# sawbench_digital_reva.net
KiCad netlist of a schematic drawn in EAGLE
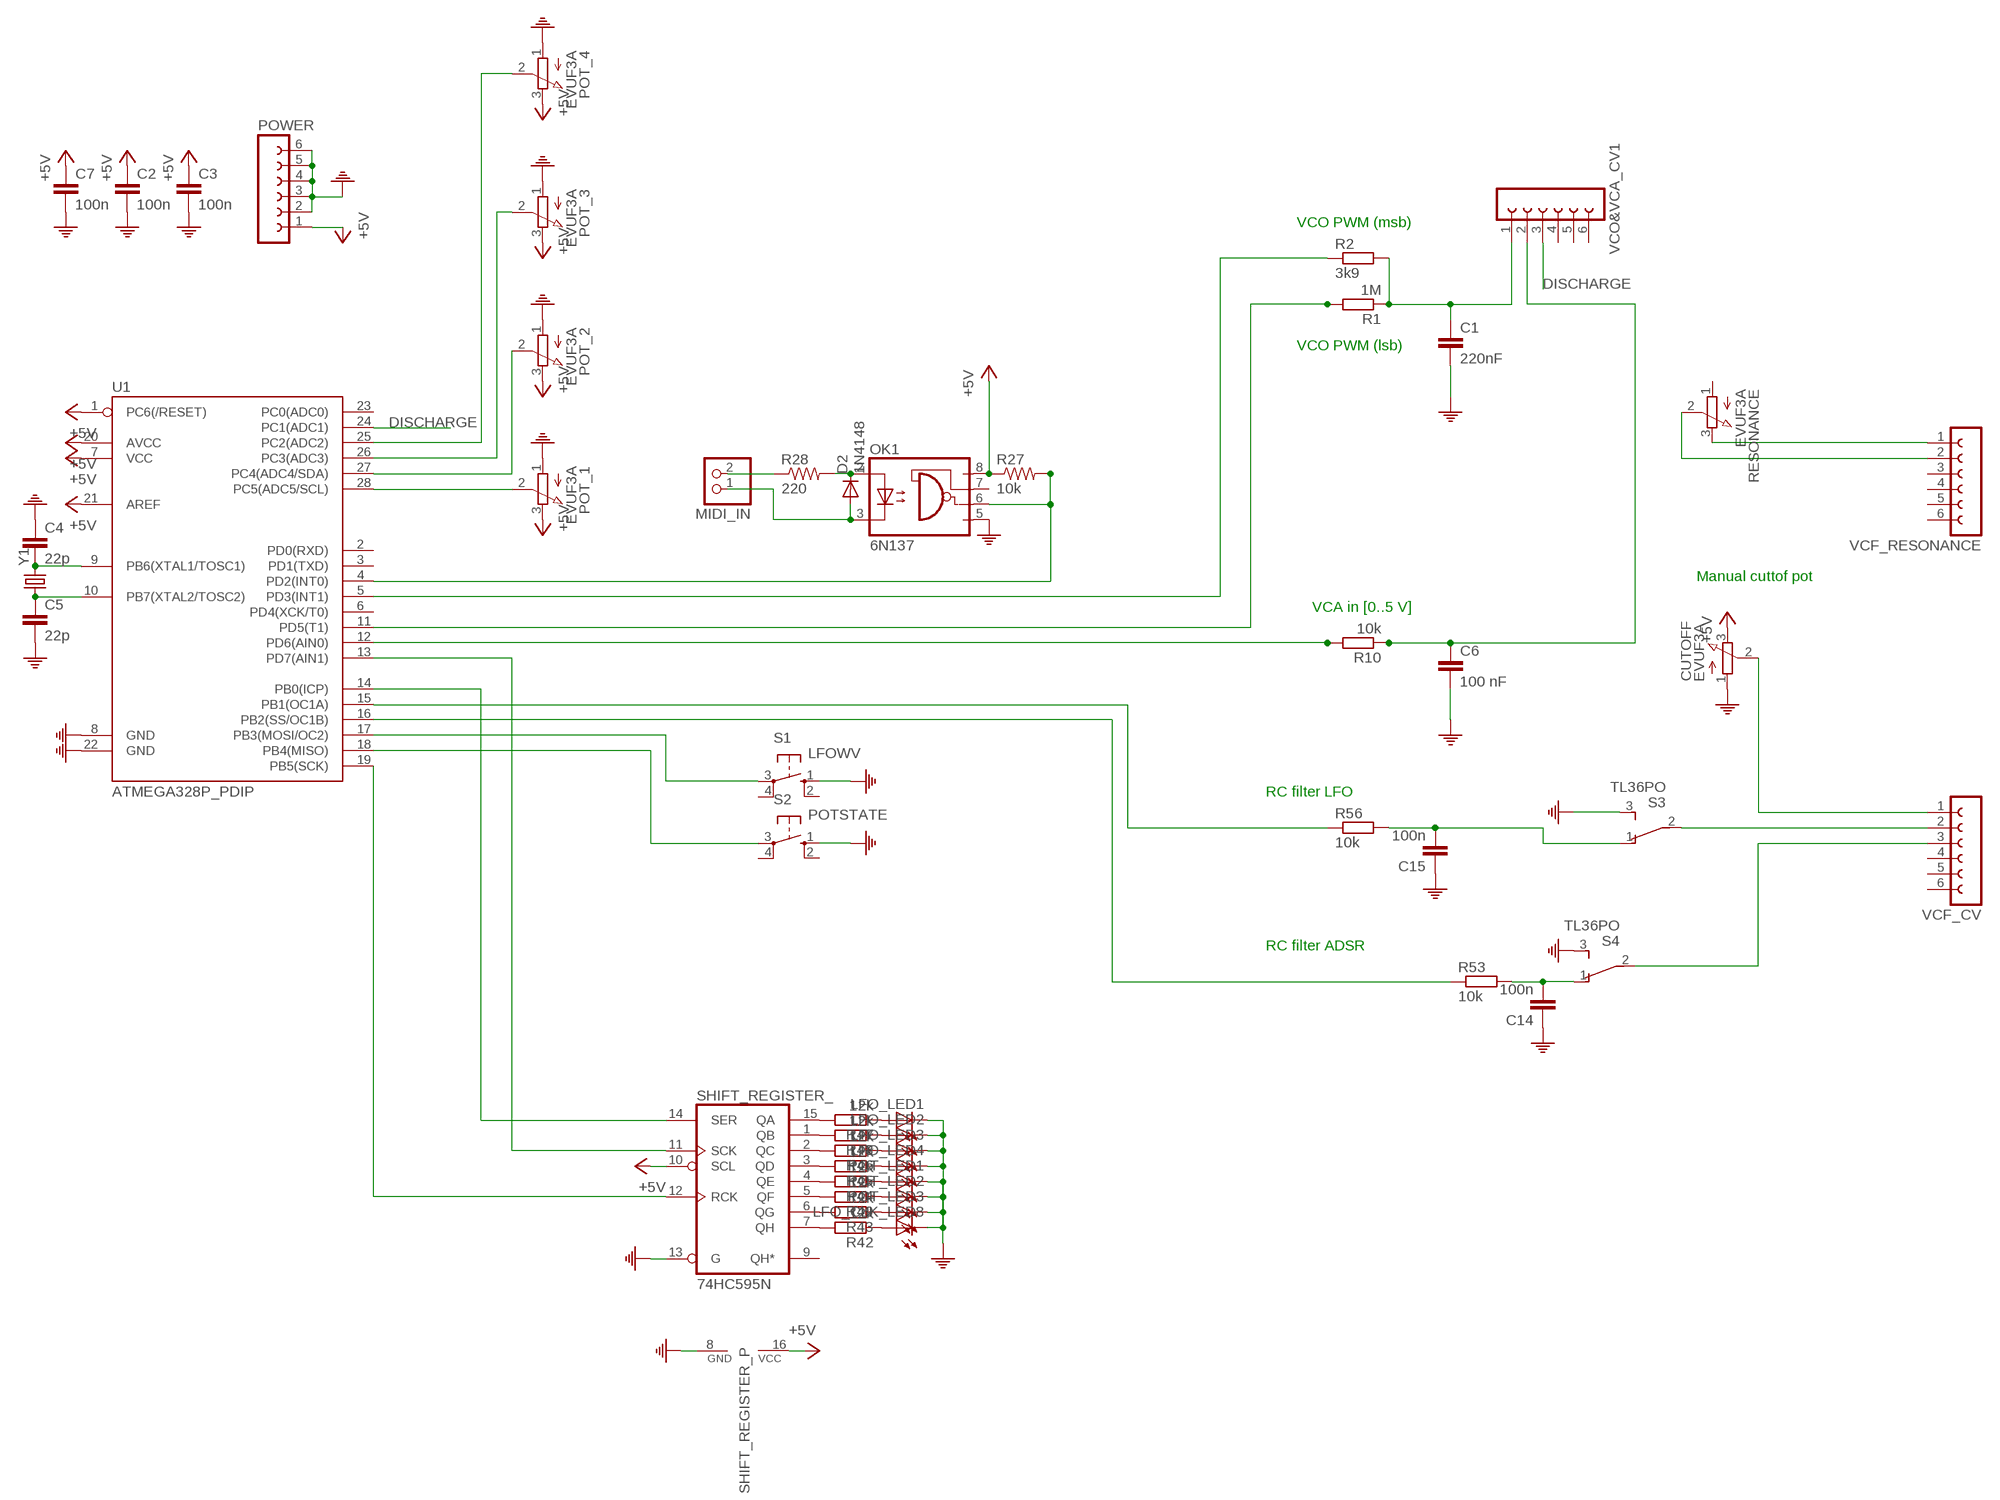
[diagram p0: schematic, sheet 1]

(export (version "E")
  (design (tool "Eeschema 10.0.6"))
  (components
    (comp (ref "C1")
      (value "220nF")
      (footprint "eagle-import:C050-024X044")
      (libsource (lib "eagle-import") (part "resistor_C-EU050-024X044"))
    )
    (comp (ref "C2")
      (value "100n")
      (footprint "eagle-import:C025-024X044")
      (libsource (lib "eagle-import") (part "C-EU025-024X044"))
    )
    (comp (ref "C3")
      (value "100n")
      (footprint "eagle-import:C025-024X044")
      (libsource (lib "eagle-import") (part "C-EU025-024X044"))
    )
    (comp (ref "C4")
      (value "22p")
      (footprint "eagle-import:C025-024X044")
      (libsource (lib "eagle-import") (part "C-EU025-024X044"))
    )
    (comp (ref "C5")
      (value "22p")
      (footprint "eagle-import:C025-024X044")
      (libsource (lib "eagle-import") (part "C-EU025-024X044"))
    )
    (comp (ref "C6")
      (value "100 nF")
      (footprint "eagle-import:C025-025X050")
      (libsource (lib "eagle-import") (part "C-EU025-025X050"))
    )
    (comp (ref "C7")
      (value "100n")
      (footprint "eagle-import:C025-024X044")
      (libsource (lib "eagle-import") (part "C-EU025-024X044"))
    )
    (comp (ref "C14")
      (value "100n")
      (footprint "eagle-import:C025-024X044")
      (libsource (lib "eagle-import") (part "resistor_C-EU025-024X044"))
    )
    (comp (ref "C15")
      (value "100n")
      (footprint "eagle-import:C025-024X044")
      (libsource (lib "eagle-import") (part "resistor_C-EU025-024X044"))
    )
    (comp (ref "CUTOFF")
      (value "EVUF3A")
      (footprint "eagle-import:EVUF")
      (libsource (lib "eagle-import") (part "EVUAF3"))
    )
    (comp (ref "D2")
      (value "1N4148")
      (footprint "eagle-import:D-5")
      (libsource (lib "eagle-import") (part "DIODE-D-5"))
    )
    (comp (ref "LFO_CLK_LED8")
      (value "LED3MM")
      (footprint "eagle-import:LED3MM")
      (libsource (lib "eagle-import") (part "LED3MM"))
    )
    (comp (ref "LFO_LED1")
      (value "LED3MM")
      (footprint "eagle-import:LED3MM")
      (libsource (lib "eagle-import") (part "LED3MM"))
    )
    (comp (ref "LFO_LED2")
      (value "LED3MM")
      (footprint "eagle-import:LED3MM")
      (libsource (lib "eagle-import") (part "LED3MM"))
    )
    (comp (ref "LFO_LED3")
      (value "LED3MM")
      (footprint "eagle-import:LED3MM")
      (libsource (lib "eagle-import") (part "LED3MM"))
    )
    (comp (ref "LFO_LED4")
      (value "LED3MM")
      (footprint "eagle-import:LED3MM")
      (libsource (lib "eagle-import") (part "LED3MM"))
    )
    (comp (ref "MIDI_IN")
      (value "PINHD-1X2")
      (footprint "eagle-import:1X02")
      (libsource (lib "eagle-import") (part "PINHD-1X2"))
    )
    (comp (ref "OK1")
      (value "6N137")
      (footprint "eagle-import:DIL08")
      (libsource (lib "eagle-import") (part "6N137"))
    )
    (comp (ref "POT_1")
      (value "EVUF3A")
      (footprint "eagle-import:EVUF")
      (libsource (lib "eagle-import") (part "EVUAF3"))
    )
    (comp (ref "POT_2")
      (value "EVUF3A")
      (footprint "eagle-import:EVUF")
      (libsource (lib "eagle-import") (part "EVUAF3"))
    )
    (comp (ref "POT_3")
      (value "EVUF3A")
      (footprint "eagle-import:EVUF")
      (libsource (lib "eagle-import") (part "EVUAF3"))
    )
    (comp (ref "POT_4")
      (value "EVUF3A")
      (footprint "eagle-import:EVUF")
      (libsource (lib "eagle-import") (part "EVUAF3"))
    )
    (comp (ref "POT_LED1")
      (value "LED3MM")
      (footprint "eagle-import:LED3MM")
      (libsource (lib "eagle-import") (part "LED3MM"))
    )
    (comp (ref "POT_LED2")
      (value "LED3MM")
      (footprint "eagle-import:LED3MM")
      (libsource (lib "eagle-import") (part "LED3MM"))
    )
    (comp (ref "POT_LED3")
      (value "LED3MM")
      (footprint "eagle-import:LED3MM")
      (libsource (lib "eagle-import") (part "LED3MM"))
    )
    (comp (ref "POWER")
      (value "FE06-1")
      (footprint "eagle-import:FE06")
      (libsource (lib "eagle-import") (part "FE06-1"))
    )
    (comp (ref "R1")
      (value "1M")
      (footprint "eagle-import:0204_7")
      (libsource (lib "eagle-import") (part "R-EU_0204/7"))
    )
    (comp (ref "R2")
      (value "3k9")
      (footprint "eagle-import:0204_7")
      (libsource (lib "eagle-import") (part "R-EU_0204/7"))
    )
    (comp (ref "R10")
      (value "10k")
      (footprint "eagle-import:0204_7")
      (libsource (lib "eagle-import") (part "R-EU_0204/7"))
    )
    (comp (ref "R27")
      (value "10k")
      (footprint "eagle-import:0204_7")
      (libsource (lib "eagle-import") (part "R-US_0204/7"))
    )
    (comp (ref "R28")
      (value "220")
      (footprint "eagle-import:0204_7")
      (libsource (lib "eagle-import") (part "R-US_0204/7"))
    )
    (comp (ref "R42")
      (value "12k")
      (footprint "eagle-import:0204_7")
      (libsource (lib "eagle-import") (part "R-EU_0204/7"))
    )
    (comp (ref "R43")
      (value "12k")
      (footprint "eagle-import:0204_7")
      (libsource (lib "eagle-import") (part "R-EU_0204/7"))
    )
    (comp (ref "R44")
      (value "12k")
      (footprint "eagle-import:0204_7")
      (libsource (lib "eagle-import") (part "R-EU_0204/7"))
    )
    (comp (ref "R45")
      (value "12k")
      (footprint "eagle-import:0204_7")
      (libsource (lib "eagle-import") (part "R-EU_0204/7"))
    )
    (comp (ref "R46")
      (value "12k")
      (footprint "eagle-import:0204_7")
      (libsource (lib "eagle-import") (part "R-EU_0204/7"))
    )
    (comp (ref "R47")
      (value "12k")
      (footprint "eagle-import:0204_7")
      (libsource (lib "eagle-import") (part "R-EU_0204/7"))
    )
    (comp (ref "R48")
      (value "12k")
      (footprint "eagle-import:0204_7")
      (libsource (lib "eagle-import") (part "R-EU_0204/7"))
    )
    (comp (ref "R49")
      (value "12k")
      (footprint "eagle-import:0204_7")
      (libsource (lib "eagle-import") (part "R-EU_0204/7"))
    )
    (comp (ref "R53")
      (value "10k")
      (footprint "eagle-import:0204_7")
      (libsource (lib "eagle-import") (part "R-EU_0204/7"))
    )
    (comp (ref "R56")
      (value "10k")
      (footprint "eagle-import:0204_7")
      (libsource (lib "eagle-import") (part "R-EU_0204/7"))
    )
    (comp (ref "RESONANCE")
      (value "EVUF3A")
      (footprint "eagle-import:EVUF")
      (libsource (lib "eagle-import") (part "EVUAF3"))
    )
    (comp (ref "S1")
      (value "LFOWV")
      (footprint "eagle-import:B3F-10XX(TASTYSWITCH)")
      (fields (field (name "MPN") "B3F-1000"))
      (libsource (lib "eagle-import") (part "10-XX"))
    )
    (comp (ref "S2")
      (value "POTSTATE")
      (footprint "eagle-import:B3F-10XX(TASTYSWITCH)")
      (fields (field (name "MPN") "B3F-1000"))
      (libsource (lib "eagle-import") (part "10-XX"))
    )
    (comp (ref "S3")
      (value "TL36PO")
      (footprint "eagle-import:TL3XPO(TASTY_CHIPS_UPDATE)")
      (libsource (lib "eagle-import") (part "TL36PO"))
    )
    (comp (ref "S4")
      (value "TL36PO")
      (footprint "eagle-import:TL3XPO(TASTY_CHIPS_UPDATE)")
      (libsource (lib "eagle-import") (part "TL36PO"))
    )
    (comp (ref "SHIFT_REGISTER_")
      (value "74HC595N")
      (footprint "eagle-import:DIL16")
      (libsource (lib "eagle-import") (part "74595NHC"))
    )
    (comp (ref "U1")
      (value "ATMEGA328P_PDIP")
      (footprint "eagle-import:DIL28-3")
      (libsource (lib "eagle-import") (part "ATMEGA328P_PDIP"))
    )
    (comp (ref "VCF_CV")
      (value "FE06-1")
      (footprint "eagle-import:FE06")
      (libsource (lib "eagle-import") (part "FE06-1"))
    )
    (comp (ref "VCF_RESONANCE")
      (value "FE06-1")
      (footprint "eagle-import:FE06")
      (libsource (lib "eagle-import") (part "FE06-1"))
    )
    (comp (ref "VCO&VCA_CV1")
      (value "FE06-1")
      (footprint "eagle-import:FE06")
      (libsource (lib "eagle-import") (part "FE06-1"))
    )
    (comp (ref "Y1")
      (value "CRYSTALHC49S")
      (footprint "eagle-import:HC49_S")
      (libsource (lib "eagle-import") (part "CRYSTALHC49S"))
    )
  )
  (nets
    (net (code "1") (name "+5V") (class "Default")
      (node (ref "C2") (pin "1") (pinfunction "1_1") (pintype "passive"))
      (node (ref "C3") (pin "1") (pinfunction "1_1") (pintype "passive"))
      (node (ref "C7") (pin "1") (pinfunction "1_1") (pintype "passive"))
      (node (ref "CUTOFF") (pin "3") (pinfunction "E_3") (pintype "passive"))
      (node (ref "OK1") (pin "8") (pinfunction "VCC_8") (pintype "passive"))
      (node (ref "POT_1") (pin "3") (pinfunction "E_3") (pintype "passive"))
      (node (ref "POT_2") (pin "3") (pinfunction "E_3") (pintype "passive"))
      (node (ref "POT_3") (pin "3") (pinfunction "E_3") (pintype "passive"))
      (node (ref "POT_4") (pin "3") (pinfunction "E_3") (pintype "passive"))
      (node (ref "POWER") (pin "1") (pinfunction "1_1") (pintype "passive"))
      (node (ref "R27") (pin "1") (pinfunction "1_1") (pintype "passive"))
      (node (ref "SHIFT_REGISTER_") (pin "10") (pinfunction "SCL_10") (pintype "input"))
      (node (ref "SHIFT_REGISTER_") (pin "16") (pinfunction "VCC_16") (pintype "power_in"))
      (node (ref "U1") (pin "1") (pinfunction "PC6(/RESET)_1") (pintype "bidirectional"))
      (node (ref "U1") (pin "20") (pinfunction "AVCC_20") (pintype "bidirectional"))
      (node (ref "U1") (pin "21") (pinfunction "AREF_21") (pintype "bidirectional"))
      (node (ref "U1") (pin "7") (pinfunction "VCC_7") (pintype "bidirectional"))
    )
    (net (code "2") (name "/DISCHARGE") (class "Default")
      (node (ref "U1") (pin "24") (pinfunction "PC1(ADC1)_24") (pintype "bidirectional"))
      (node (ref "VCO&VCA_CV1") (pin "3") (pinfunction "3_3") (pintype "passive"))
    )
    (net (code "3") (name "Net-(C1-Pad1)") (class "Default")
      (node (ref "C1") (pin "1") (pinfunction "1_1") (pintype "passive"))
      (node (ref "R1") (pin "1") (pinfunction "1_1") (pintype "passive"))
      (node (ref "R2") (pin "2") (pinfunction "2_2") (pintype "passive"))
      (node (ref "VCO&VCA_CV1") (pin "1") (pinfunction "1_1") (pintype "passive"))
    )
    (net (code "4") (name "Net-(C6-Pad1)") (class "Default")
      (node (ref "C6") (pin "1") (pinfunction "1_1") (pintype "passive"))
      (node (ref "R10") (pin "1") (pinfunction "1_1") (pintype "passive"))
      (node (ref "VCO&VCA_CV1") (pin "2") (pinfunction "2_2") (pintype "passive"))
    )
    (net (code "5") (name "Net-(CUTOFF-S)") (class "Default")
      (node (ref "CUTOFF") (pin "2") (pinfunction "S_2") (pintype "passive"))
      (node (ref "VCF_CV") (pin "1") (pinfunction "1_1") (pintype "passive"))
    )
    (net (code "6") (name "Net-(LFO_CLK_LED8-PadA)") (class "Default")
      (node (ref "LFO_CLK_LED8") (pin "A") (pinfunction "A_A") (pintype "passive"))
      (node (ref "R42") (pin "1") (pinfunction "1_1") (pintype "passive"))
    )
    (net (code "7") (name "Net-(LFO_LED1-PadA)") (class "Default")
      (node (ref "LFO_LED1") (pin "A") (pinfunction "A_A") (pintype "passive"))
      (node (ref "R47") (pin "1") (pinfunction "1_1") (pintype "passive"))
    )
    (net (code "8") (name "Net-(LFO_LED2-PadA)") (class "Default")
      (node (ref "LFO_LED2") (pin "A") (pinfunction "A_A") (pintype "passive"))
      (node (ref "R48") (pin "1") (pinfunction "1_1") (pintype "passive"))
    )
    (net (code "9") (name "Net-(LFO_LED3-PadA)") (class "Default")
      (node (ref "LFO_LED3") (pin "A") (pinfunction "A_A") (pintype "passive"))
      (node (ref "R46") (pin "1") (pinfunction "1_1") (pintype "passive"))
    )
    (net (code "10") (name "Net-(LFO_LED4-PadA)") (class "Default")
      (node (ref "LFO_LED4") (pin "A") (pinfunction "A_A") (pintype "passive"))
      (node (ref "R45") (pin "1") (pinfunction "1_1") (pintype "passive"))
    )
    (net (code "11") (name "Net-(MIDI_IN-Pad2)") (class "Default")
      (node (ref "MIDI_IN") (pin "2") (pinfunction "2_2") (pintype "passive"))
      (node (ref "R28") (pin "1") (pinfunction "1_1") (pintype "passive"))
    )
    (net (code "12") (name "Net-(OK1-A)") (class "Default")
      (node (ref "D2") (pin "C") (pinfunction "C_C") (pintype "passive"))
      (node (ref "OK1") (pin "2") (pinfunction "A_2") (pintype "passive"))
      (node (ref "R28") (pin "2") (pinfunction "2_2") (pintype "passive"))
    )
    (net (code "13") (name "Net-(OK1-C)") (class "Default")
      (node (ref "D2") (pin "A") (pinfunction "A_A") (pintype "passive"))
      (node (ref "MIDI_IN") (pin "1") (pinfunction "1_1") (pintype "passive"))
      (node (ref "OK1") (pin "3") (pinfunction "C_3") (pintype "passive"))
    )
    (net (code "14") (name "Net-(OK1-VO)") (class "Default")
      (node (ref "OK1") (pin "6") (pinfunction "VO_6") (pintype "passive"))
      (node (ref "R27") (pin "2") (pinfunction "2_2") (pintype "passive"))
      (node (ref "U1") (pin "4") (pinfunction "PD2(INT0)_4") (pintype "bidirectional"))
    )
    (net (code "15") (name "Net-(POT_1-S)") (class "Default")
      (node (ref "POT_1") (pin "2") (pinfunction "S_2") (pintype "passive"))
      (node (ref "U1") (pin "28") (pinfunction "PC5(ADC5/SCL)_28") (pintype "bidirectional"))
    )
    (net (code "16") (name "Net-(POT_2-S)") (class "Default")
      (node (ref "POT_2") (pin "2") (pinfunction "S_2") (pintype "passive"))
      (node (ref "U1") (pin "27") (pinfunction "PC4(ADC4/SDA)_27") (pintype "bidirectional"))
    )
    (net (code "17") (name "Net-(POT_3-S)") (class "Default")
      (node (ref "POT_3") (pin "2") (pinfunction "S_2") (pintype "passive"))
      (node (ref "U1") (pin "26") (pinfunction "PC3(ADC3)_26") (pintype "bidirectional"))
    )
    (net (code "18") (name "Net-(POT_4-S)") (class "Default")
      (node (ref "POT_4") (pin "2") (pinfunction "S_2") (pintype "passive"))
      (node (ref "U1") (pin "25") (pinfunction "PC2(ADC2)_25") (pintype "bidirectional"))
    )
    (net (code "19") (name "Net-(POT_LED1-PadA)") (class "Default")
      (node (ref "POT_LED1") (pin "A") (pinfunction "A_A") (pintype "passive"))
      (node (ref "R44") (pin "1") (pinfunction "1_1") (pintype "passive"))
    )
    (net (code "20") (name "Net-(POT_LED2-PadA)") (class "Default")
      (node (ref "POT_LED2") (pin "A") (pinfunction "A_A") (pintype "passive"))
      (node (ref "R49") (pin "1") (pinfunction "1_1") (pintype "passive"))
    )
    (net (code "21") (name "Net-(POT_LED3-PadA)") (class "Default")
      (node (ref "POT_LED3") (pin "A") (pinfunction "A_A") (pintype "passive"))
      (node (ref "R43") (pin "1") (pinfunction "1_1") (pintype "passive"))
    )
    (net (code "22") (name "Net-(RESONANCE-E)") (class "Default")
      (node (ref "RESONANCE") (pin "3") (pinfunction "E_3") (pintype "passive"))
      (node (ref "VCF_RESONANCE") (pin "1") (pinfunction "1_1") (pintype "passive"))
    )
    (net (code "23") (name "Net-(RESONANCE-S)") (class "Default")
      (node (ref "RESONANCE") (pin "2") (pinfunction "S_2") (pintype "passive"))
      (node (ref "VCF_RESONANCE") (pin "2") (pinfunction "2_2") (pintype "passive"))
    )
    (net (code "24") (name "Net-(S1-P)") (class "Default")
      (node (ref "S1") (pin "3") (pinfunction "P_3") (pintype "passive"))
      (node (ref "U1") (pin "17") (pinfunction "PB3(MOSI/OC2)_17") (pintype "bidirectional"))
    )
    (net (code "25") (name "Net-(S2-P)") (class "Default")
      (node (ref "S2") (pin "3") (pinfunction "P_3") (pintype "passive"))
      (node (ref "U1") (pin "18") (pinfunction "PB4(MISO)_18") (pintype "bidirectional"))
    )
    (net (code "26") (name "Net-(S3-O)") (class "Default")
      (node (ref "C15") (pin "2") (pinfunction "2_2") (pintype "passive"))
      (node (ref "R56") (pin "2") (pinfunction "2_2") (pintype "passive"))
      (node (ref "S3") (pin "1") (pinfunction "O_1") (pintype "passive"))
    )
    (net (code "27") (name "Net-(S3-P)") (class "Default")
      (node (ref "S3") (pin "2") (pinfunction "P_2") (pintype "passive"))
      (node (ref "VCF_CV") (pin "2") (pinfunction "2_2") (pintype "passive"))
    )
    (net (code "28") (name "Net-(S4-O)") (class "Default")
      (node (ref "C14") (pin "2") (pinfunction "2_2") (pintype "passive"))
      (node (ref "R53") (pin "2") (pinfunction "2_2") (pintype "passive"))
      (node (ref "S4") (pin "1") (pinfunction "O_1") (pintype "passive"))
    )
    (net (code "29") (name "Net-(S4-P)") (class "Default")
      (node (ref "S4") (pin "2") (pinfunction "P_2") (pintype "passive"))
      (node (ref "VCF_CV") (pin "3") (pinfunction "3_3") (pintype "passive"))
    )
    (net (code "30") (name "Net-(SHIFT_REGISTER_A-QA)") (class "Default")
      (node (ref "R47") (pin "2") (pinfunction "2_2") (pintype "passive"))
      (node (ref "SHIFT_REGISTER_") (pin "15") (pinfunction "QA_15") (pintype "tri_state"))
    )
    (net (code "31") (name "Net-(SHIFT_REGISTER_A-QB)") (class "Default")
      (node (ref "R48") (pin "2") (pinfunction "2_2") (pintype "passive"))
      (node (ref "SHIFT_REGISTER_") (pin "1") (pinfunction "QB_1") (pintype "tri_state"))
    )
    (net (code "32") (name "Net-(SHIFT_REGISTER_A-QC)") (class "Default")
      (node (ref "R46") (pin "2") (pinfunction "2_2") (pintype "passive"))
      (node (ref "SHIFT_REGISTER_") (pin "2") (pinfunction "QC_2") (pintype "tri_state"))
    )
    (net (code "33") (name "Net-(SHIFT_REGISTER_A-QD)") (class "Default")
      (node (ref "R45") (pin "2") (pinfunction "2_2") (pintype "passive"))
      (node (ref "SHIFT_REGISTER_") (pin "3") (pinfunction "QD_3") (pintype "tri_state"))
    )
    (net (code "34") (name "Net-(SHIFT_REGISTER_A-QE)") (class "Default")
      (node (ref "R44") (pin "2") (pinfunction "2_2") (pintype "passive"))
      (node (ref "SHIFT_REGISTER_") (pin "4") (pinfunction "QE_4") (pintype "tri_state"))
    )
    (net (code "35") (name "Net-(SHIFT_REGISTER_A-QF)") (class "Default")
      (node (ref "R49") (pin "2") (pinfunction "2_2") (pintype "passive"))
      (node (ref "SHIFT_REGISTER_") (pin "5") (pinfunction "QF_5") (pintype "tri_state"))
    )
    (net (code "36") (name "Net-(SHIFT_REGISTER_A-QG)") (class "Default")
      (node (ref "R43") (pin "2") (pinfunction "2_2") (pintype "passive"))
      (node (ref "SHIFT_REGISTER_") (pin "6") (pinfunction "QG_6") (pintype "tri_state"))
    )
    (net (code "37") (name "Net-(SHIFT_REGISTER_A-QH)") (class "Default")
      (node (ref "R42") (pin "2") (pinfunction "2_2") (pintype "passive"))
      (node (ref "SHIFT_REGISTER_") (pin "7") (pinfunction "QH_7") (pintype "tri_state"))
    )
    (net (code "38") (name "Net-(SHIFT_REGISTER_A-RCK)") (class "Default")
      (node (ref "SHIFT_REGISTER_") (pin "12") (pinfunction "RCK_12") (pintype "input"))
      (node (ref "U1") (pin "19") (pinfunction "PB5(SCK)_19") (pintype "bidirectional"))
    )
    (net (code "39") (name "Net-(SHIFT_REGISTER_A-SCK)") (class "Default")
      (node (ref "SHIFT_REGISTER_") (pin "11") (pinfunction "SCK_11") (pintype "input"))
      (node (ref "U1") (pin "13") (pinfunction "PD7(AIN1)_13") (pintype "bidirectional"))
    )
    (net (code "40") (name "Net-(SHIFT_REGISTER_A-SER)") (class "Default")
      (node (ref "SHIFT_REGISTER_") (pin "14") (pinfunction "SER_14") (pintype "input"))
      (node (ref "U1") (pin "14") (pinfunction "PB0(ICP)_14") (pintype "bidirectional"))
    )
    (net (code "41") (name "Net-(U1-PB1(OC1A))") (class "Default")
      (node (ref "R56") (pin "1") (pinfunction "1_1") (pintype "passive"))
      (node (ref "U1") (pin "15") (pinfunction "PB1(OC1A)_15") (pintype "bidirectional"))
    )
    (net (code "42") (name "Net-(U1-PB2(SS{slash}OC1B))") (class "Default")
      (node (ref "R53") (pin "1") (pinfunction "1_1") (pintype "passive"))
      (node (ref "U1") (pin "16") (pinfunction "PB2(SS/OC1B)_16") (pintype "bidirectional"))
    )
    (net (code "43") (name "Net-(U1-PB6(XTAL1{slash}TOSC1))") (class "Default")
      (node (ref "C4") (pin "2") (pinfunction "2_2") (pintype "passive"))
      (node (ref "U1") (pin "9") (pinfunction "PB6(XTAL1/TOSC1)_9") (pintype "bidirectional"))
      (node (ref "Y1") (pin "2") (pinfunction "2_2") (pintype "passive"))
    )
    (net (code "44") (name "Net-(U1-PB7(XTAL2{slash}TOSC2))") (class "Default")
      (node (ref "C5") (pin "1") (pinfunction "1_1") (pintype "passive"))
      (node (ref "U1") (pin "10") (pinfunction "PB7(XTAL2/TOSC2)_10") (pintype "bidirectional"))
      (node (ref "Y1") (pin "1") (pinfunction "1_1") (pintype "passive"))
    )
    (net (code "45") (name "Net-(U1-PD3(INT1))") (class "Default")
      (node (ref "R2") (pin "1") (pinfunction "1_1") (pintype "passive"))
      (node (ref "U1") (pin "5") (pinfunction "PD3(INT1)_5") (pintype "bidirectional"))
    )
    (net (code "46") (name "Net-(U1-PD5(T1))") (class "Default")
      (node (ref "R1") (pin "2") (pinfunction "2_2") (pintype "passive"))
      (node (ref "U1") (pin "11") (pinfunction "PD5(T1)_11") (pintype "bidirectional"))
    )
    (net (code "47") (name "Net-(U1-PD6(AIN0))") (class "Default")
      (node (ref "R10") (pin "2") (pinfunction "2_2") (pintype "passive"))
      (node (ref "U1") (pin "12") (pinfunction "PD6(AIN0)_12") (pintype "bidirectional"))
    )
    (net (code "48") (name "PE") (class "Default")
      (node (ref "C1") (pin "2") (pinfunction "2_2") (pintype "passive"))
      (node (ref "C14") (pin "1") (pinfunction "1_1") (pintype "passive"))
      (node (ref "C15") (pin "1") (pinfunction "1_1") (pintype "passive"))
      (node (ref "C2") (pin "2") (pinfunction "2_2") (pintype "passive"))
      (node (ref "C3") (pin "2") (pinfunction "2_2") (pintype "passive"))
      (node (ref "C4") (pin "1") (pinfunction "1_1") (pintype "passive"))
      (node (ref "C5") (pin "2") (pinfunction "2_2") (pintype "passive"))
      (node (ref "C6") (pin "2") (pinfunction "2_2") (pintype "passive"))
      (node (ref "C7") (pin "2") (pinfunction "2_2") (pintype "passive"))
      (node (ref "CUTOFF") (pin "1") (pinfunction "A_1") (pintype "passive"))
      (node (ref "LFO_CLK_LED8") (pin "K") (pinfunction "C_K") (pintype "passive"))
      (node (ref "LFO_LED1") (pin "K") (pinfunction "C_K") (pintype "passive"))
      (node (ref "LFO_LED2") (pin "K") (pinfunction "C_K") (pintype "passive"))
      (node (ref "LFO_LED3") (pin "K") (pinfunction "C_K") (pintype "passive"))
      (node (ref "LFO_LED4") (pin "K") (pinfunction "C_K") (pintype "passive"))
      (node (ref "OK1") (pin "5") (pinfunction "GND_5") (pintype "passive"))
      (node (ref "POT_1") (pin "1") (pinfunction "A_1") (pintype "passive"))
      (node (ref "POT_2") (pin "1") (pinfunction "A_1") (pintype "passive"))
      (node (ref "POT_3") (pin "1") (pinfunction "A_1") (pintype "passive"))
      (node (ref "POT_4") (pin "1") (pinfunction "A_1") (pintype "passive"))
      (node (ref "POT_LED1") (pin "K") (pinfunction "C_K") (pintype "passive"))
      (node (ref "POT_LED2") (pin "K") (pinfunction "C_K") (pintype "passive"))
      (node (ref "POT_LED3") (pin "K") (pinfunction "C_K") (pintype "passive"))
      (node (ref "POWER") (pin "2") (pinfunction "2_2") (pintype "passive"))
      (node (ref "POWER") (pin "3") (pinfunction "3_3") (pintype "passive"))
      (node (ref "POWER") (pin "4") (pinfunction "4_4") (pintype "passive"))
      (node (ref "POWER") (pin "5") (pinfunction "5_5") (pintype "passive"))
      (node (ref "POWER") (pin "6") (pinfunction "6_6") (pintype "passive"))
      (node (ref "S1") (pin "1") (pinfunction "S_1") (pintype "passive"))
      (node (ref "S2") (pin "1") (pinfunction "S_1") (pintype "passive"))
      (node (ref "S3") (pin "3") (pinfunction "S_3") (pintype "passive"))
      (node (ref "S4") (pin "3") (pinfunction "S_3") (pintype "passive"))
      (node (ref "SHIFT_REGISTER_") (pin "13") (pinfunction "G_13") (pintype "input"))
      (node (ref "SHIFT_REGISTER_") (pin "8") (pinfunction "GND_8") (pintype "power_in"))
      (node (ref "U1") (pin "22") (pinfunction "GND_22") (pintype "bidirectional"))
      (node (ref "U1") (pin "8") (pinfunction "GND_8") (pintype "bidirectional"))
    )
    (net (code "49") (name "unconnected-(OK1-VE-Pad7)") (class "Default")
      (node (ref "OK1") (pin "7") (pinfunction "VE_7") (pintype "passive"))
    )
    (net (code "50") (name "unconnected-(RESONANCE-A-Pad1)") (class "Default")
      (node (ref "RESONANCE") (pin "1") (pinfunction "A_1") (pintype "passive"))
    )
    (net (code "51") (name "unconnected-(S1-P1-Pad4)") (class "Default")
      (node (ref "S1") (pin "4") (pinfunction "P1_4") (pintype "passive"))
    )
    (net (code "52") (name "unconnected-(S1-S1-Pad2)") (class "Default")
      (node (ref "S1") (pin "2") (pinfunction "S1_2") (pintype "passive"))
    )
    (net (code "53") (name "unconnected-(S2-P1-Pad4)") (class "Default")
      (node (ref "S2") (pin "4") (pinfunction "P1_4") (pintype "passive"))
    )
    (net (code "54") (name "unconnected-(S2-S1-Pad2)") (class "Default")
      (node (ref "S2") (pin "2") (pinfunction "S1_2") (pintype "passive"))
    )
    (net (code "55") (name "unconnected-(SHIFT_REGISTER_A-QH*-Pad9)") (class "Default")
      (node (ref "SHIFT_REGISTER_") (pin "9") (pinfunction "QH*_9") (pintype "tri_state"))
    )
    (net (code "56") (name "unconnected-(U1-PC0(ADC0)-Pad23)") (class "Default")
      (node (ref "U1") (pin "23") (pinfunction "PC0(ADC0)_23") (pintype "bidirectional"))
    )
    (net (code "57") (name "unconnected-(U1-PD0(RXD)-Pad2)") (class "Default")
      (node (ref "U1") (pin "2") (pinfunction "PD0(RXD)_2") (pintype "bidirectional"))
    )
    (net (code "58") (name "unconnected-(U1-PD1(TXD)-Pad3)") (class "Default")
      (node (ref "U1") (pin "3") (pinfunction "PD1(TXD)_3") (pintype "bidirectional"))
    )
    (net (code "59") (name "unconnected-(U1-PD4(XCK{slash}T0)-Pad6)") (class "Default")
      (node (ref "U1") (pin "6") (pinfunction "PD4(XCK/T0)_6") (pintype "bidirectional"))
    )
    (net (code "60") (name "unconnected-(VCF_CV-Pad4)") (class "Default")
      (node (ref "VCF_CV") (pin "4") (pinfunction "4_4") (pintype "passive"))
    )
    (net (code "61") (name "unconnected-(VCF_CV-Pad5)") (class "Default")
      (node (ref "VCF_CV") (pin "5") (pinfunction "5_5") (pintype "passive"))
    )
    (net (code "62") (name "unconnected-(VCF_CV-Pad6)") (class "Default")
      (node (ref "VCF_CV") (pin "6") (pinfunction "6_6") (pintype "passive"))
    )
    (net (code "63") (name "unconnected-(VCF_RESONANCE-Pad3)") (class "Default")
      (node (ref "VCF_RESONANCE") (pin "3") (pinfunction "3_3") (pintype "passive"))
    )
    (net (code "64") (name "unconnected-(VCF_RESONANCE-Pad4)") (class "Default")
      (node (ref "VCF_RESONANCE") (pin "4") (pinfunction "4_4") (pintype "passive"))
    )
    (net (code "65") (name "unconnected-(VCF_RESONANCE-Pad5)") (class "Default")
      (node (ref "VCF_RESONANCE") (pin "5") (pinfunction "5_5") (pintype "passive"))
    )
    (net (code "66") (name "unconnected-(VCF_RESONANCE-Pad6)") (class "Default")
      (node (ref "VCF_RESONANCE") (pin "6") (pinfunction "6_6") (pintype "passive"))
    )
    (net (code "67") (name "unconnected-(VCO&VCA_CV1-Pad4)") (class "Default")
      (node (ref "VCO&VCA_CV1") (pin "4") (pinfunction "4_4") (pintype "passive"))
    )
    (net (code "68") (name "unconnected-(VCO&VCA_CV1-Pad5)") (class "Default")
      (node (ref "VCO&VCA_CV1") (pin "5") (pinfunction "5_5") (pintype "passive"))
    )
    (net (code "69") (name "unconnected-(VCO&VCA_CV1-Pad6)") (class "Default")
      (node (ref "VCO&VCA_CV1") (pin "6") (pinfunction "6_6") (pintype "passive"))
    )
  )
)
